# Teensy_LC_meter.net
KiCad netlist of a schematic drawn in EAGLE
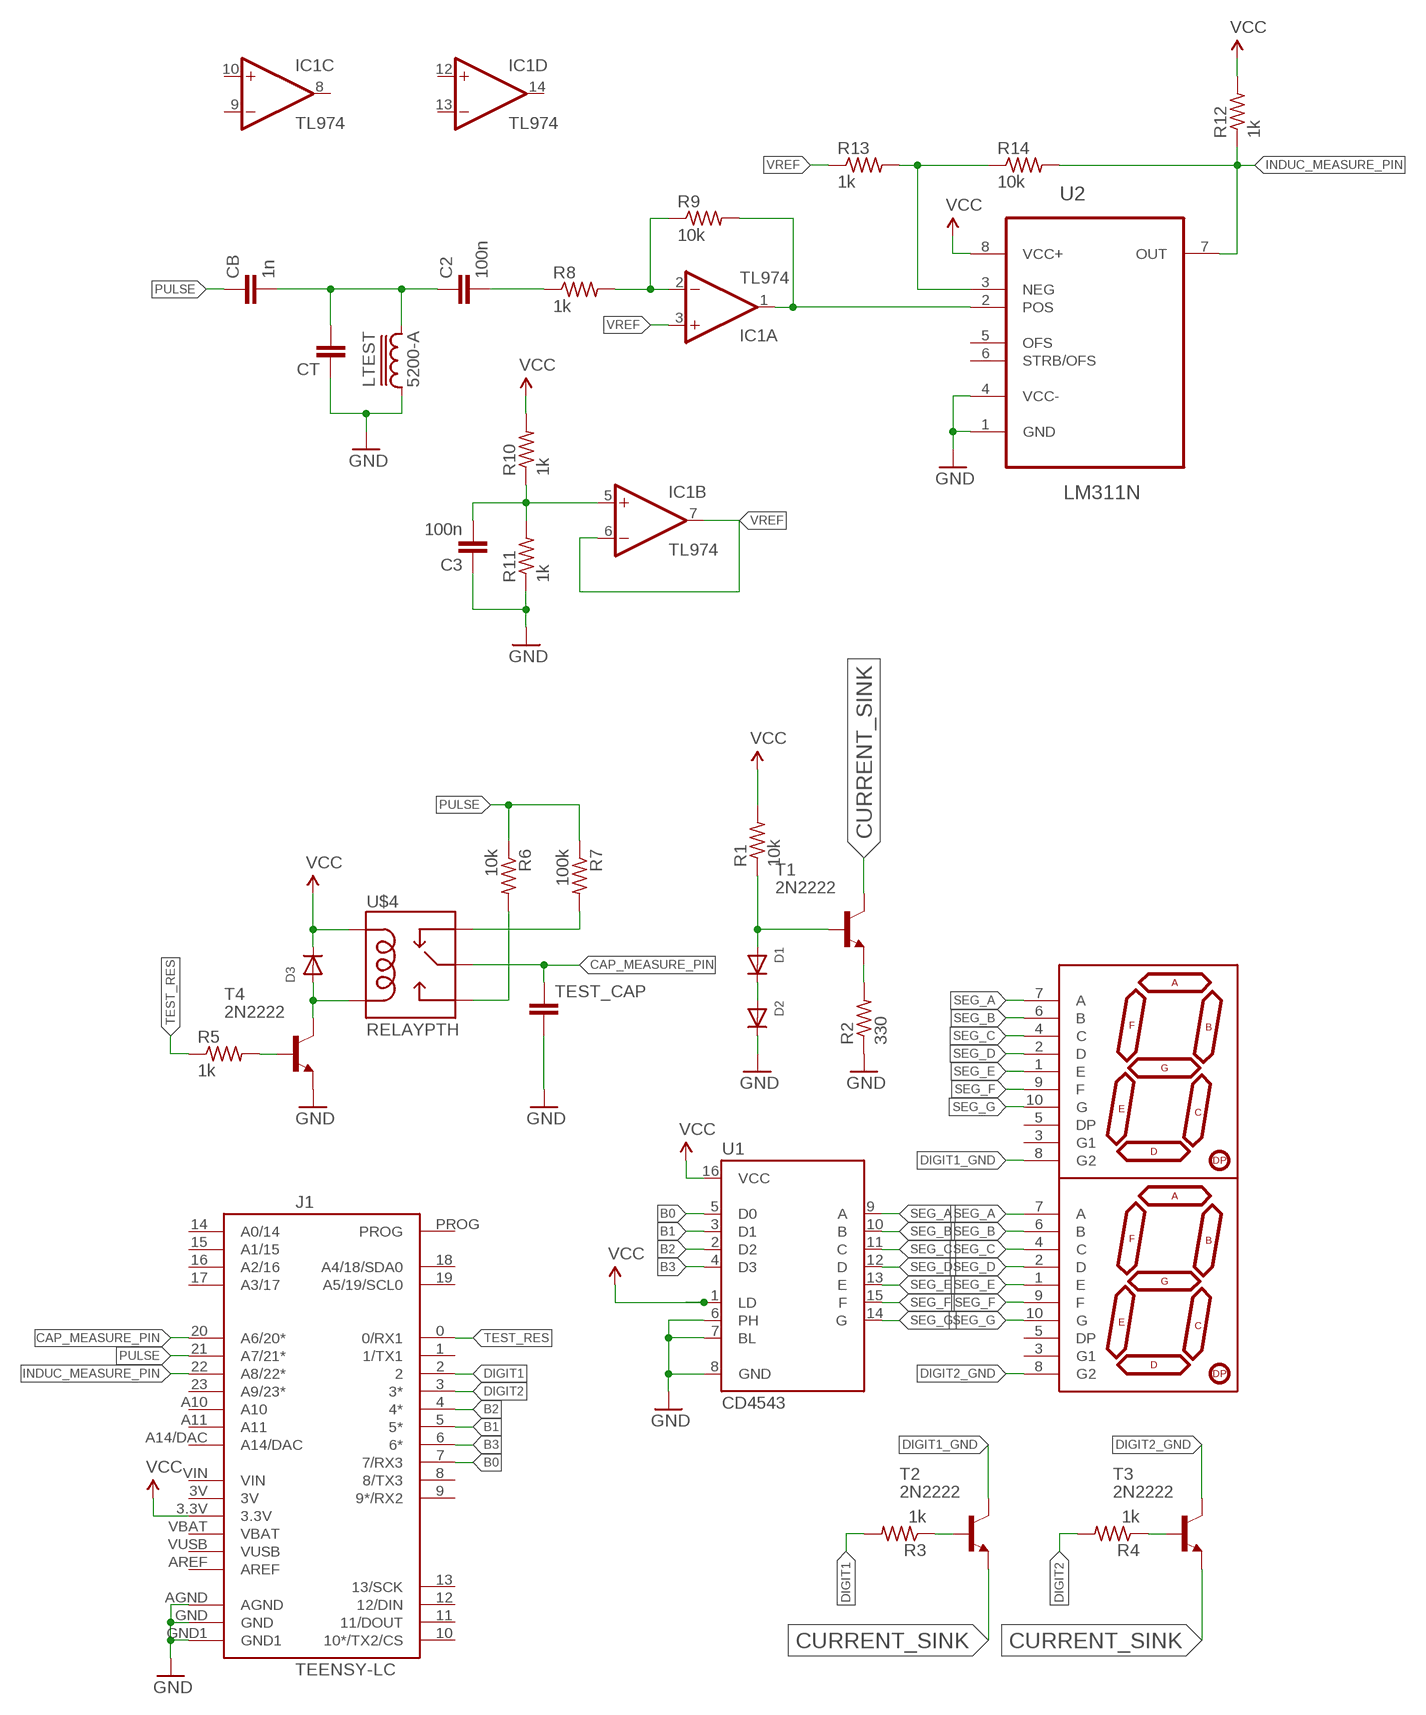
[diagram p0: schematic, sheet 1]

(export (version "E")
  (design (tool "Eeschema 10.0.6"))
  (components
    (comp (ref "C2")
      (value "100n")
      (footprint "eagle-import:CAP-PTH-SMALL")
      (libsource (lib "eagle-import") (part "CAPPTH"))
    )
    (comp (ref "C3")
      (value "100n")
      (footprint "eagle-import:CAP-PTH-SMALL")
      (libsource (lib "eagle-import") (part "CAPPTH"))
    )
    (comp (ref "CB")
      (value "1n")
      (footprint "eagle-import:CAP-PTH-SMALL")
      (libsource (lib "eagle-import") (part "CAPPTH"))
    )
    (comp (ref "CT")
      (value "CAPPTH")
      (footprint "eagle-import:CAP-PTH-SMALL")
      (libsource (lib "eagle-import") (part "CAPPTH"))
    )
    (comp (ref "D1")
      (value "DIODEDO-1N4148")
      (footprint "eagle-import:DO-1N4148")
      (libsource (lib "eagle-import") (part "DIODEDO-1N4148"))
    )
    (comp (ref "D2")
      (value "DIODEDO-1N4148")
      (footprint "eagle-import:DO-1N4148")
      (libsource (lib "eagle-import") (part "DIODEDO-1N4148"))
    )
    (comp (ref "D3")
      (value "DIODEDO-1N4148")
      (footprint "eagle-import:DO-1N4148")
      (libsource (lib "eagle-import") (part "DIODEDO-1N4148"))
    )
    (comp (ref "IC1")
      (value "TL974")
      (footprint "eagle-import:SO14")
      (libsource (lib "eagle-import") (part "QUAD_OPAMPD"))
    )
    (comp (ref "J1")
      (value "TEENSY-LC")
      (footprint "eagle-import:TEENSY-3.1_NOSILK")
      (libsource (lib "eagle-import") (part "TEENSY-3.1NOSILK"))
    )
    (comp (ref "LTEST")
      (value "5200-A")
      (footprint "eagle-import:5200-A")
      (libsource (lib "eagle-import") (part "5200-A"))
    )
    (comp (ref "R1")
      (value "10k")
      (footprint "eagle-import:0805-THM")
      (libsource (lib "eagle-import") (part "FLIPFLOP-RES"))
    )
    (comp (ref "R2")
      (value "330")
      (footprint "eagle-import:0805-THM")
      (libsource (lib "eagle-import") (part "FLIPFLOP-RES"))
    )
    (comp (ref "R3")
      (value "1k")
      (footprint "eagle-import:0805-THM")
      (libsource (lib "eagle-import") (part "FLIPFLOP-RES"))
    )
    (comp (ref "R4")
      (value "1k")
      (footprint "eagle-import:0805-THM")
      (libsource (lib "eagle-import") (part "FLIPFLOP-RES"))
    )
    (comp (ref "R5")
      (value "1k")
      (footprint "eagle-import:0805-THM")
      (libsource (lib "eagle-import") (part "FLIPFLOP-RES"))
    )
    (comp (ref "R6")
      (value "10k")
      (footprint "eagle-import:0805-THM")
      (libsource (lib "eagle-import") (part "FLIPFLOP-RES"))
    )
    (comp (ref "R7")
      (value "100k")
      (footprint "eagle-import:0805-THM")
      (libsource (lib "eagle-import") (part "FLIPFLOP-RES"))
    )
    (comp (ref "R8")
      (value "1k")
      (footprint "eagle-import:0805-THM")
      (libsource (lib "eagle-import") (part "FLIPFLOP-RES"))
    )
    (comp (ref "R9")
      (value "10k")
      (footprint "eagle-import:0805-THM")
      (libsource (lib "eagle-import") (part "FLIPFLOP-RES"))
    )
    (comp (ref "R10")
      (value "1k")
      (footprint "eagle-import:0805-THM")
      (libsource (lib "eagle-import") (part "FLIPFLOP-RES"))
    )
    (comp (ref "R11")
      (value "1k")
      (footprint "eagle-import:0805-THM")
      (libsource (lib "eagle-import") (part "FLIPFLOP-RES"))
    )
    (comp (ref "R12")
      (value "1k")
      (footprint "eagle-import:0805-THM")
      (libsource (lib "eagle-import") (part "FLIPFLOP-RES"))
    )
    (comp (ref "R13")
      (value "1k")
      (footprint "eagle-import:0805-THM")
      (libsource (lib "eagle-import") (part "FLIPFLOP-RES"))
    )
    (comp (ref "R14")
      (value "10k")
      (footprint "eagle-import:0805-THM")
      (libsource (lib "eagle-import") (part "FLIPFLOP-RES"))
    )
    (comp (ref "T1")
      (value "2N2222")
      (footprint "eagle-import:TO92-EBC-OVAL")
      (libsource (lib "eagle-import") (part "2N2222"))
    )
    (comp (ref "T2")
      (value "2N2222")
      (footprint "eagle-import:TO92-EBC-OVAL")
      (libsource (lib "eagle-import") (part "2N2222"))
    )
    (comp (ref "T3")
      (value "2N2222")
      (footprint "eagle-import:TO92-EBC-OVAL")
      (libsource (lib "eagle-import") (part "2N2222"))
    )
    (comp (ref "T4")
      (value "2N2222")
      (footprint "eagle-import:TO92-EBC-OVAL")
      (libsource (lib "eagle-import") (part "2N2222"))
    )
    (comp (ref "TEST_CAP")
      (value "CAPPTH")
      (footprint "eagle-import:CAP-PTH-SMALL")
      (libsource (lib "eagle-import") (part "CAPPTH"))
    )
    (comp (ref "U$2")
      (value "7-SEGMENT-DISPLAY-1\"-REDEZ")
      (footprint "eagle-import:7-SEGMENT-1_PTH-EZ")
      (libsource (lib "eagle-import") (part "7-SEGMENT-DISPLAY-1{dblquote}-REDEZ"))
    )
    (comp (ref "U$3")
      (value "7-SEGMENT-DISPLAY-1\"-REDEZ")
      (footprint "eagle-import:7-SEGMENT-1_PTH-EZ")
      (libsource (lib "eagle-import") (part "7-SEGMENT-DISPLAY-1{dblquote}-REDEZ"))
    )
    (comp (ref "U$4")
      (value "RELAYPTH")
      (footprint "eagle-import:RELAY-G5Q")
      (libsource (lib "eagle-import") (part "RELAYPTH"))
    )
    (comp (ref "U1")
      (value "CD4543")
      (footprint "eagle-import:DIL16")
      (libsource (lib "eagle-import") (part "HEF4543PTH"))
    )
    (comp (ref "U2")
      (value "LM311N")
      (footprint "eagle-import:DIP254P762X480-8")
      (libsource (lib "eagle-import") (part "LM311N"))
    )
  )
  (nets
    (net (code "1") (name "B0") (class "Default")
      (node (ref "J1") (pin "7") (pinfunction "7/RX3_7") (pintype "bidirectional"))
      (node (ref "U1") (pin "5") (pinfunction "D0_5") (pintype "bidirectional"))
    )
    (net (code "2") (name "B1") (class "Default")
      (node (ref "J1") (pin "5") (pinfunction "5*_5") (pintype "bidirectional"))
      (node (ref "U1") (pin "3") (pinfunction "D1_3") (pintype "bidirectional"))
    )
    (net (code "3") (name "B2") (class "Default")
      (node (ref "J1") (pin "4") (pinfunction "4*_4") (pintype "bidirectional"))
      (node (ref "U1") (pin "2") (pinfunction "D2_2") (pintype "bidirectional"))
    )
    (net (code "4") (name "B3") (class "Default")
      (node (ref "J1") (pin "6") (pinfunction "6*_6") (pintype "bidirectional"))
      (node (ref "U1") (pin "4") (pinfunction "D3_4") (pintype "bidirectional"))
    )
    (net (code "5") (name "CAP_MEASURE_PIN") (class "Default")
      (node (ref "J1") (pin "20") (pinfunction "A6/20*_20") (pintype "bidirectional"))
      (node (ref "TEST_CAP") (pin "1") (pinfunction "1_1") (pintype "passive"))
      (node (ref "U$4") (pin "2") (pinfunction "MAIN_2") (pintype "bidirectional"))
    )
    (net (code "6") (name "CURRENT_SINK") (class "Default")
      (node (ref "T1") (pin "C") (pinfunction "C_C") (pintype "passive"))
      (node (ref "T2") (pin "E") (pinfunction "E_E") (pintype "passive"))
      (node (ref "T3") (pin "E") (pinfunction "E_E") (pintype "passive"))
    )
    (net (code "7") (name "DIGIT1") (class "Default")
      (node (ref "J1") (pin "2") (pinfunction "2_2") (pintype "bidirectional"))
      (node (ref "R3") (pin "2") (pinfunction "2_2") (pintype "passive"))
    )
    (net (code "8") (name "DIGIT1_GND") (class "Default")
      (node (ref "T2") (pin "C") (pinfunction "C_C") (pintype "passive"))
      (node (ref "U$2") (pin "8") (pinfunction "G2_8") (pintype "bidirectional"))
    )
    (net (code "9") (name "DIGIT2") (class "Default")
      (node (ref "J1") (pin "3") (pinfunction "3*_3") (pintype "bidirectional"))
      (node (ref "R4") (pin "2") (pinfunction "2_2") (pintype "passive"))
    )
    (net (code "10") (name "DIGIT2_GND") (class "Default")
      (node (ref "T3") (pin "C") (pinfunction "C_C") (pintype "passive"))
      (node (ref "U$3") (pin "8") (pinfunction "G2_8") (pintype "bidirectional"))
    )
    (net (code "11") (name "GND") (class "Default")
      (node (ref "C3") (pin "1") (pinfunction "1_1") (pintype "passive"))
      (node (ref "CT") (pin "1") (pinfunction "1_1") (pintype "passive"))
      (node (ref "D2") (pin "C") (pinfunction "C_C") (pintype "passive"))
      (node (ref "J1") (pin "AGND") (pinfunction "AGND_AGND") (pintype "bidirectional"))
      (node (ref "J1") (pin "GND") (pinfunction "GND_GND") (pintype "bidirectional"))
      (node (ref "J1") (pin "GND1") (pinfunction "GND1_GND1") (pintype "bidirectional"))
      (node (ref "LTEST") (pin "1") (pinfunction "1_1") (pintype "passive"))
      (node (ref "R11") (pin "1") (pinfunction "1_1") (pintype "passive"))
      (node (ref "R2") (pin "1") (pinfunction "1_1") (pintype "passive"))
      (node (ref "T4") (pin "E") (pinfunction "E_E") (pintype "passive"))
      (node (ref "TEST_CAP") (pin "2") (pinfunction "2_2") (pintype "passive"))
      (node (ref "U1") (pin "6") (pinfunction "PH_6") (pintype "bidirectional"))
      (node (ref "U1") (pin "7") (pinfunction "BL_7") (pintype "bidirectional"))
      (node (ref "U1") (pin "8") (pinfunction "GND_8") (pintype "bidirectional"))
      (node (ref "U2") (pin "1") (pinfunction "GND_1") (pintype "passive"))
      (node (ref "U2") (pin "4") (pinfunction "VCC-_4") (pintype "power_in"))
    )
    (net (code "12") (name "INDUC_MEASURE_PIN") (class "Default")
      (node (ref "J1") (pin "22") (pinfunction "A8/22*_22") (pintype "bidirectional"))
      (node (ref "R12") (pin "1") (pinfunction "1_1") (pintype "passive"))
      (node (ref "R14") (pin "2") (pinfunction "2_2") (pintype "passive"))
      (node (ref "U2") (pin "7") (pinfunction "OUT_7") (pintype "output"))
    )
    (net (code "13") (name "Net-(C2-Pad1)") (class "Default")
      (node (ref "C2") (pin "1") (pinfunction "1_1") (pintype "passive"))
      (node (ref "CB") (pin "2") (pinfunction "2_2") (pintype "passive"))
      (node (ref "CT") (pin "2") (pinfunction "2_2") (pintype "passive"))
      (node (ref "LTEST") (pin "2") (pinfunction "2_2") (pintype "passive"))
    )
    (net (code "14") (name "Net-(C2-Pad2)") (class "Default")
      (node (ref "C2") (pin "2") (pinfunction "2_2") (pintype "passive"))
      (node (ref "R8") (pin "1") (pinfunction "1_1") (pintype "passive"))
    )
    (net (code "15") (name "Net-(D1-PadA)") (class "Default")
      (node (ref "D1") (pin "A") (pinfunction "A_A") (pintype "passive"))
      (node (ref "R1") (pin "1") (pinfunction "1_1") (pintype "passive"))
      (node (ref "T1") (pin "B") (pinfunction "B_B") (pintype "passive"))
    )
    (net (code "16") (name "Net-(D1-PadC)") (class "Default")
      (node (ref "D1") (pin "C") (pinfunction "C_C") (pintype "passive"))
      (node (ref "D2") (pin "A") (pinfunction "A_A") (pintype "passive"))
    )
    (net (code "17") (name "Net-(IC1A--IN)") (class "Default")
      (node (ref "IC1") (pin "2") (pinfunction "-IN_2") (pintype "input"))
      (node (ref "R8") (pin "2") (pinfunction "2_2") (pintype "passive"))
      (node (ref "R9") (pin "1") (pinfunction "1_1") (pintype "passive"))
    )
    (net (code "18") (name "Net-(IC1A-OUT)") (class "Default")
      (node (ref "IC1") (pin "1") (pinfunction "OUT_1") (pintype "output"))
      (node (ref "R9") (pin "2") (pinfunction "2_2") (pintype "passive"))
      (node (ref "U2") (pin "2") (pinfunction "POS_2") (pintype "input"))
    )
    (net (code "19") (name "Net-(IC1B-+IN)") (class "Default")
      (node (ref "C3") (pin "2") (pinfunction "2_2") (pintype "passive"))
      (node (ref "IC1") (pin "5") (pinfunction "+IN_5") (pintype "input"))
      (node (ref "R10") (pin "1") (pinfunction "1_1") (pintype "passive"))
      (node (ref "R11") (pin "2") (pinfunction "2_2") (pintype "passive"))
    )
    (net (code "20") (name "Net-(R2-Pad2)") (class "Default")
      (node (ref "R2") (pin "2") (pinfunction "2_2") (pintype "passive"))
      (node (ref "T1") (pin "E") (pinfunction "E_E") (pintype "passive"))
    )
    (net (code "21") (name "Net-(R3-Pad1)") (class "Default")
      (node (ref "R3") (pin "1") (pinfunction "1_1") (pintype "passive"))
      (node (ref "T2") (pin "B") (pinfunction "B_B") (pintype "passive"))
    )
    (net (code "22") (name "Net-(R4-Pad1)") (class "Default")
      (node (ref "R4") (pin "1") (pinfunction "1_1") (pintype "passive"))
      (node (ref "T3") (pin "B") (pinfunction "B_B") (pintype "passive"))
    )
    (net (code "23") (name "Net-(R5-Pad2)") (class "Default")
      (node (ref "R5") (pin "2") (pinfunction "2_2") (pintype "passive"))
      (node (ref "T4") (pin "B") (pinfunction "B_B") (pintype "passive"))
    )
    (net (code "24") (name "Net-(U$4-COIL2)") (class "Default")
      (node (ref "D3") (pin "A") (pinfunction "A_A") (pintype "passive"))
      (node (ref "T4") (pin "C") (pinfunction "C_C") (pintype "passive"))
      (node (ref "U$4") (pin "1") (pinfunction "COIL2_1") (pintype "bidirectional"))
    )
    (net (code "25") (name "Net-(U$4-NC)") (class "Default")
      (node (ref "R7") (pin "2") (pinfunction "2_2") (pintype "passive"))
      (node (ref "U$4") (pin "4") (pinfunction "NC_4") (pintype "bidirectional"))
    )
    (net (code "26") (name "Net-(U$4-NO)") (class "Default")
      (node (ref "R6") (pin "2") (pinfunction "2_2") (pintype "passive"))
      (node (ref "U$4") (pin "3") (pinfunction "NO_3") (pintype "bidirectional"))
    )
    (net (code "27") (name "Net-(U2-NEG)") (class "Default")
      (node (ref "R13") (pin "2") (pinfunction "2_2") (pintype "passive"))
      (node (ref "R14") (pin "1") (pinfunction "1_1") (pintype "passive"))
      (node (ref "U2") (pin "3") (pinfunction "NEG_3") (pintype "input"))
    )
    (net (code "28") (name "PULSE") (class "Default")
      (node (ref "CB") (pin "1") (pinfunction "1_1") (pintype "passive"))
      (node (ref "J1") (pin "21") (pinfunction "A7/21*_21") (pintype "bidirectional"))
      (node (ref "R6") (pin "1") (pinfunction "1_1") (pintype "passive"))
      (node (ref "R7") (pin "1") (pinfunction "1_1") (pintype "passive"))
    )
    (net (code "29") (name "SEG_A") (class "Default")
      (node (ref "U$2") (pin "7") (pinfunction "A_7") (pintype "bidirectional"))
      (node (ref "U$3") (pin "7") (pinfunction "A_7") (pintype "bidirectional"))
      (node (ref "U1") (pin "9") (pinfunction "A_9") (pintype "bidirectional"))
    )
    (net (code "30") (name "SEG_B") (class "Default")
      (node (ref "U$2") (pin "6") (pinfunction "B_6") (pintype "bidirectional"))
      (node (ref "U$3") (pin "6") (pinfunction "B_6") (pintype "bidirectional"))
      (node (ref "U1") (pin "10") (pinfunction "B_10") (pintype "bidirectional"))
    )
    (net (code "31") (name "SEG_C") (class "Default")
      (node (ref "U$2") (pin "4") (pinfunction "C_4") (pintype "bidirectional"))
      (node (ref "U$3") (pin "4") (pinfunction "C_4") (pintype "bidirectional"))
      (node (ref "U1") (pin "11") (pinfunction "C_11") (pintype "bidirectional"))
    )
    (net (code "32") (name "SEG_D") (class "Default")
      (node (ref "U$2") (pin "2") (pinfunction "D_2") (pintype "bidirectional"))
      (node (ref "U$3") (pin "2") (pinfunction "D_2") (pintype "bidirectional"))
      (node (ref "U1") (pin "12") (pinfunction "D_12") (pintype "bidirectional"))
    )
    (net (code "33") (name "SEG_E") (class "Default")
      (node (ref "U$2") (pin "1") (pinfunction "E_1") (pintype "bidirectional"))
      (node (ref "U$3") (pin "1") (pinfunction "E_1") (pintype "bidirectional"))
      (node (ref "U1") (pin "13") (pinfunction "E_13") (pintype "bidirectional"))
    )
    (net (code "34") (name "SEG_F") (class "Default")
      (node (ref "U$2") (pin "9") (pinfunction "F_9") (pintype "bidirectional"))
      (node (ref "U$3") (pin "9") (pinfunction "F_9") (pintype "bidirectional"))
      (node (ref "U1") (pin "15") (pinfunction "F_15") (pintype "bidirectional"))
    )
    (net (code "35") (name "SEG_G") (class "Default")
      (node (ref "U$2") (pin "10") (pinfunction "G_10") (pintype "bidirectional"))
      (node (ref "U$3") (pin "10") (pinfunction "G_10") (pintype "bidirectional"))
      (node (ref "U1") (pin "14") (pinfunction "G_14") (pintype "bidirectional"))
    )
    (net (code "36") (name "TEST_RES") (class "Default")
      (node (ref "J1") (pin "0") (pinfunction "0/RX1_0") (pintype "bidirectional"))
      (node (ref "R5") (pin "1") (pinfunction "1_1") (pintype "passive"))
    )
    (net (code "37") (name "VCC") (class "Default")
      (node (ref "D3") (pin "C") (pinfunction "C_C") (pintype "passive"))
      (node (ref "J1") (pin "3.3V") (pinfunction "3.3V_3.3V") (pintype "bidirectional"))
      (node (ref "R1") (pin "2") (pinfunction "2_2") (pintype "passive"))
      (node (ref "R10") (pin "2") (pinfunction "2_2") (pintype "passive"))
      (node (ref "R12") (pin "2") (pinfunction "2_2") (pintype "passive"))
      (node (ref "U$4") (pin "5") (pinfunction "COIL1_5") (pintype "bidirectional"))
      (node (ref "U1") (pin "1") (pinfunction "LD_1") (pintype "bidirectional"))
      (node (ref "U1") (pin "16") (pinfunction "VCC_16") (pintype "bidirectional"))
      (node (ref "U2") (pin "8") (pinfunction "VCC+_8") (pintype "power_in"))
    )
    (net (code "38") (name "VREF") (class "Default")
      (node (ref "IC1") (pin "3") (pinfunction "+IN_3") (pintype "input"))
      (node (ref "IC1") (pin "6") (pinfunction "-IN_6") (pintype "input"))
      (node (ref "IC1") (pin "7") (pinfunction "OUT_7") (pintype "output"))
      (node (ref "R13") (pin "1") (pinfunction "1_1") (pintype "passive"))
    )
    (net (code "39") (name "unconnected-(IC1C-+IN-Pad10)") (class "Default")
      (node (ref "IC1") (pin "10") (pinfunction "+IN_10") (pintype "input"))
    )
    (net (code "40") (name "unconnected-(IC1C--IN-Pad9)") (class "Default")
      (node (ref "IC1") (pin "9") (pinfunction "-IN_9") (pintype "input"))
    )
    (net (code "41") (name "unconnected-(IC1C-OUT-Pad8)") (class "Default")
      (node (ref "IC1") (pin "8") (pinfunction "OUT_8") (pintype "output"))
    )
    (net (code "42") (name "unconnected-(IC1D-+IN-Pad12)") (class "Default")
      (node (ref "IC1") (pin "12") (pinfunction "+IN_12") (pintype "input"))
    )
    (net (code "43") (name "unconnected-(IC1D--IN-Pad13)") (class "Default")
      (node (ref "IC1") (pin "13") (pinfunction "-IN_13") (pintype "input"))
    )
    (net (code "44") (name "unconnected-(IC1D-OUT-Pad14)") (class "Default")
      (node (ref "IC1") (pin "14") (pinfunction "OUT_14") (pintype "output"))
    )
    (net (code "45") (name "unconnected-(J1-1{slash}TX1-Pad1)") (class "Default")
      (node (ref "J1") (pin "1") (pinfunction "1/TX1_1") (pintype "bidirectional"))
    )
    (net (code "46") (name "unconnected-(J1-8{slash}TX3-Pad8)") (class "Default")
      (node (ref "J1") (pin "8") (pinfunction "8/TX3_8") (pintype "bidirectional"))
    )
    (net (code "47") (name "unconnected-(J1-9*{slash}RX2-Pad9)") (class "Default")
      (node (ref "J1") (pin "9") (pinfunction "9*/RX2_9") (pintype "bidirectional"))
    )
    (net (code "48") (name "unconnected-(J1-10*{slash}TX2{slash}CS-Pad10)") (class "Default")
      (node (ref "J1") (pin "10") (pinfunction "10*/TX2/CS_10") (pintype "bidirectional"))
    )
    (net (code "49") (name "unconnected-(J1-11{slash}DOUT-Pad11)") (class "Default")
      (node (ref "J1") (pin "11") (pinfunction "11/DOUT_11") (pintype "bidirectional"))
    )
    (net (code "50") (name "unconnected-(J1-12{slash}DIN-Pad12)") (class "Default")
      (node (ref "J1") (pin "12") (pinfunction "12/DIN_12") (pintype "bidirectional"))
    )
    (net (code "51") (name "unconnected-(J1-13{slash}SCK-Pad13)") (class "Default")
      (node (ref "J1") (pin "13") (pinfunction "13/SCK_13") (pintype "bidirectional"))
    )
    (net (code "52") (name "unconnected-(J1-A0{slash}14-Pad14)") (class "Default")
      (node (ref "J1") (pin "14") (pinfunction "A0/14_14") (pintype "bidirectional"))
    )
    (net (code "53") (name "unconnected-(J1-A1{slash}15-Pad15)") (class "Default")
      (node (ref "J1") (pin "15") (pinfunction "A1/15_15") (pintype "bidirectional"))
    )
    (net (code "54") (name "unconnected-(J1-A2{slash}16-Pad16)") (class "Default")
      (node (ref "J1") (pin "16") (pinfunction "A2/16_16") (pintype "bidirectional"))
    )
    (net (code "55") (name "unconnected-(J1-A3{slash}17-Pad17)") (class "Default")
      (node (ref "J1") (pin "17") (pinfunction "A3/17_17") (pintype "bidirectional"))
    )
    (net (code "56") (name "unconnected-(J1-A4{slash}18{slash}SDA0-Pad18)") (class "Default")
      (node (ref "J1") (pin "18") (pinfunction "A4/18/SDA0_18") (pintype "bidirectional"))
    )
    (net (code "57") (name "unconnected-(J1-A5{slash}19{slash}SCL0-Pad19)") (class "Default")
      (node (ref "J1") (pin "19") (pinfunction "A5/19/SCL0_19") (pintype "bidirectional"))
    )
    (net (code "58") (name "unconnected-(J1-A9{slash}23*-Pad23)") (class "Default")
      (node (ref "J1") (pin "23") (pinfunction "A9/23*_23") (pintype "bidirectional"))
    )
    (net (code "59") (name "unconnected-(J1-Pad3V)") (class "Default")
      (node (ref "J1") (pin "3V") (pinfunction "3V_3V") (pintype "bidirectional"))
    )
    (net (code "60") (name "unconnected-(J1-PadA10)") (class "Default")
      (node (ref "J1") (pin "A10") (pinfunction "A10_A10") (pintype "bidirectional"))
    )
    (net (code "61") (name "unconnected-(J1-PadA11)") (class "Default")
      (node (ref "J1") (pin "A11") (pinfunction "A11_A11") (pintype "bidirectional"))
    )
    (net (code "62") (name "unconnected-(J1-PadA14{slash}DAC)") (class "Default")
      (node (ref "J1") (pin "A14/DAC") (pinfunction "A14/DAC_A14/DAC") (pintype "bidirectional"))
    )
    (net (code "63") (name "unconnected-(J1-PadAREF)") (class "Default")
      (node (ref "J1") (pin "AREF") (pinfunction "AREF_AREF") (pintype "bidirectional"))
    )
    (net (code "64") (name "unconnected-(J1-PadPROG)") (class "Default")
      (node (ref "J1") (pin "PROG") (pinfunction "PROG_PROG") (pintype "bidirectional"))
    )
    (net (code "65") (name "unconnected-(J1-PadVBAT)") (class "Default")
      (node (ref "J1") (pin "VBAT") (pinfunction "VBAT_VBAT") (pintype "bidirectional"))
    )
    (net (code "66") (name "unconnected-(J1-PadVIN)") (class "Default")
      (node (ref "J1") (pin "VIN") (pinfunction "VIN_VIN") (pintype "bidirectional"))
    )
    (net (code "67") (name "unconnected-(J1-PadVUSB)") (class "Default")
      (node (ref "J1") (pin "VUSB") (pinfunction "VUSB_VUSB") (pintype "bidirectional"))
    )
    (net (code "68") (name "unconnected-(U$2-DP-Pad5)") (class "Default")
      (node (ref "U$2") (pin "5") (pinfunction "DP_5") (pintype "bidirectional"))
    )
    (net (code "69") (name "unconnected-(U$2-G1-Pad3)") (class "Default")
      (node (ref "U$2") (pin "3") (pinfunction "G1_3") (pintype "bidirectional"))
    )
    (net (code "70") (name "unconnected-(U$3-DP-Pad5)") (class "Default")
      (node (ref "U$3") (pin "5") (pinfunction "DP_5") (pintype "bidirectional"))
    )
    (net (code "71") (name "unconnected-(U$3-G1-Pad3)") (class "Default")
      (node (ref "U$3") (pin "3") (pinfunction "G1_3") (pintype "bidirectional"))
    )
    (net (code "72") (name "unconnected-(U2-OFS-Pad5)") (class "Default")
      (node (ref "U2") (pin "5") (pinfunction "OFS_5") (pintype "passive"))
    )
    (net (code "73") (name "unconnected-(U2-STRB{slash}OFS-Pad6)") (class "Default")
      (node (ref "U2") (pin "6") (pinfunction "STRB/OFS_6") (pintype "passive"))
    )
  )
)
